# OneRealayNode.net
KiCad netlist of a schematic drawn in Altium Designer
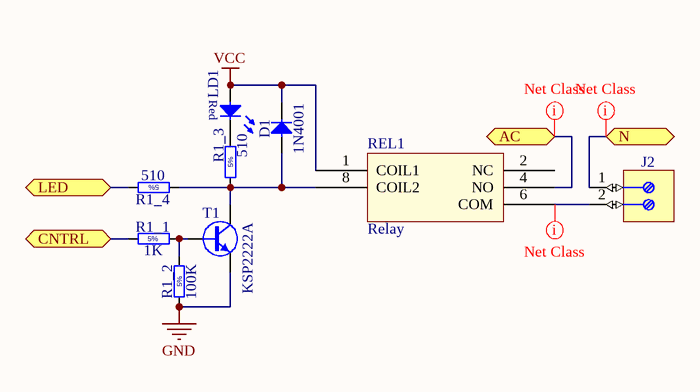
[diagram p0: OneRealayNode.SchDoc]

(export (version "E")
  (design (tool "Eeschema 10.0.6"))
  (components
    (comp (ref "D1")
      (value "1N4001")
      (footprint "DO-41")
      (description "Diode")
      (fields
        (field (name "PART NUMBER") "1N4007")
        (field (name "VOLTAGE") "1000V")
        (field (name "AUTHOR") "CERN DEM JLC")
      )
      (libsource (lib "ICs And Semiconductors") (part "Diode"))
    )
    (comp (ref "J2")
      (value "Terminal")
      (footprint "WIELAND_25.161.0253.0")
      (description "Terminal Block, 2 Positions, Screw Connection")
      (fields
        (field (name "PART NUMBER") "WIELAND_25.161.0253.0")
        (field (name "MANUFACTURER") "WIELAND")
        (field (name "AUTHOR") "CERN DEM JLC")
      )
      (libsource (lib "Connectors") (part "Terminal Block_2 Positions_Screw Connection"))
    )
    (comp (ref "LD1")
      (value "Red")
      (footprint "LED_3MM_RED_1C-2A")
      (description "LED Red 1C 2A")
      (fields
        (field (name "PART NUMBER") "LED_AVAGO_HLMP-1700")
        (field (name "MANUFACTURER") "AVAGO TECHNOLOGIES")
        (field (name "AUTHOR") "CERN DEM JLC")
      )
      (libsource (lib "ICs And Semiconductors") (part "LED Red 1C 2A"))
    )
    (comp (ref "R1_1")
      (value "1K")
      (footprint "RES_ARCOL_RCC025")
      (description "Resistor - 5%")
      (fields
        (field (name "PART NUMBER") "RCF_5K1_5%_0.25W_+10-6PPM_ARCOL_RCC025")
        (field (name "POWER") "0.25W")
        (field (name "AUTHOR") "CERN DEM JLC")
      )
      (libsource (lib "Resistors") (part "Resistor - 5%"))
    )
    (comp (ref "R1_2")
      (value "100K")
      (footprint "RES_ARCOL_RCC025")
      (description "Resistor - 5%")
      (fields
        (field (name "PART NUMBER") "RCF_5K1_5%_0.25W_+10-6PPM_ARCOL_RCC025")
        (field (name "POWER") "0.25W")
        (field (name "AUTHOR") "CERN DEM JLC")
      )
      (libsource (lib "Resistors") (part "Resistor - 5%"))
    )
    (comp (ref "R1_3")
      (value "510")
      (footprint "RES_ARCOL_RCC025")
      (description "Resistor - 5%")
      (fields
        (field (name "PART NUMBER") "RCF_5K1_5%_0.25W_+10-6PPM_ARCOL_RCC025")
        (field (name "POWER") "0.25W")
        (field (name "AUTHOR") "CERN DEM JLC")
      )
      (libsource (lib "Resistors") (part "Resistor - 5%"))
    )
    (comp (ref "R1_4")
      (value "510")
      (footprint "RES_ARCOL_RCC025")
      (description "Resistor - 5%")
      (fields
        (field (name "PART NUMBER") "RCF_5K1_5%_0.25W_+10-6PPM_ARCOL_RCC025")
        (field (name "POWER") "0.25W")
        (field (name "AUTHOR") "CERN DEM JLC")
      )
      (libsource (lib "Resistors") (part "Resistor - 5%"))
    )
    (comp (ref "REL1") (value "Relay") (footprint "RP78602") (libsource (lib "SCH_Lib") (part "Relay")))
    (comp (ref "T1")
      (value "KSP2222A")
      (footprint "TO-92AA-P254")
      (description "NPN Transistor")
      (fields
        (field (name "PART NUMBER") "ZTX653")
        (field (name "MANUFACTURER") "ZETEX SEMICONDUCTORS")
        (field (name "AUTHOR") "CERN DEM JMW")
      )
      (libsource (lib "ICs And Semiconductors") (part "NPN E1 B2 C3"))
    )
  )
  (nets
    (net (code "1") (name "/AC") (class "Default")
      (node (ref "REL1") (pin "4") (pinfunction "NO_4") (pintype "passive"))
    )
    (net (code "2") (name "/CNTRL") (class "Default")
      (node (ref "R1_1") (pin "1") (pinfunction "1_1") (pintype "passive"))
    )
    (net (code "3") (name "/LED") (class "Default")
      (node (ref "R1_4") (pin "2") (pinfunction "2_2") (pintype "passive"))
    )
    (net (code "4") (name "/N") (class "Default")
      (node (ref "J2") (pin "1") (pinfunction "1_1") (pintype "bidirectional"))
    )
    (net (code "5") (name "GND") (class "Default")
      (node (ref "R1_2") (pin "1") (pinfunction "1_1") (pintype "passive"))
      (node (ref "T1") (pin "1") (pinfunction "E_1") (pintype "passive"))
    )
    (net (code "6") (name "Net-(D1-A)") (class "Default")
      (node (ref "D1") (pin "2") (pinfunction "A_2") (pintype "passive"))
      (node (ref "R1_3") (pin "1") (pinfunction "1_1") (pintype "passive"))
      (node (ref "R1_4") (pin "1") (pinfunction "1_1") (pintype "passive"))
      (node (ref "REL1") (pin "8") (pinfunction "COIL2_8") (pintype "passive"))
      (node (ref "T1") (pin "3") (pinfunction "C_3") (pintype "passive"))
    )
    (net (code "7") (name "Net-(LD1-C)") (class "Default")
      (node (ref "LD1") (pin "1") (pinfunction "C_1") (pintype "passive"))
      (node (ref "R1_3") (pin "2") (pinfunction "2_2") (pintype "passive"))
    )
    (net (code "8") (name "Net-(REL1-COM)") (class "Default")
      (node (ref "J2") (pin "2") (pinfunction "2_2") (pintype "bidirectional"))
      (node (ref "REL1") (pin "6") (pinfunction "COM_6") (pintype "passive"))
    )
    (net (code "9") (name "Net-(T1-B)") (class "Default")
      (node (ref "R1_1") (pin "2") (pinfunction "2_2") (pintype "passive"))
      (node (ref "R1_2") (pin "2") (pinfunction "2_2") (pintype "passive"))
      (node (ref "T1") (pin "2") (pinfunction "B_2") (pintype "passive"))
    )
    (net (code "10") (name "VCC") (class "Default")
      (node (ref "D1") (pin "1") (pinfunction "C_1") (pintype "passive"))
      (node (ref "LD1") (pin "2") (pinfunction "A_2") (pintype "passive"))
      (node (ref "REL1") (pin "1") (pinfunction "COIL1_1") (pintype "passive"))
    )
    (net (code "11") (name "unconnected-(REL1-NC-Pad2)") (class "Default")
      (node (ref "REL1") (pin "2") (pinfunction "NC_2") (pintype "passive"))
    )
  )
)
